# 270_rev_00.net
KiCad netlist of a schematic drawn in EAGLE
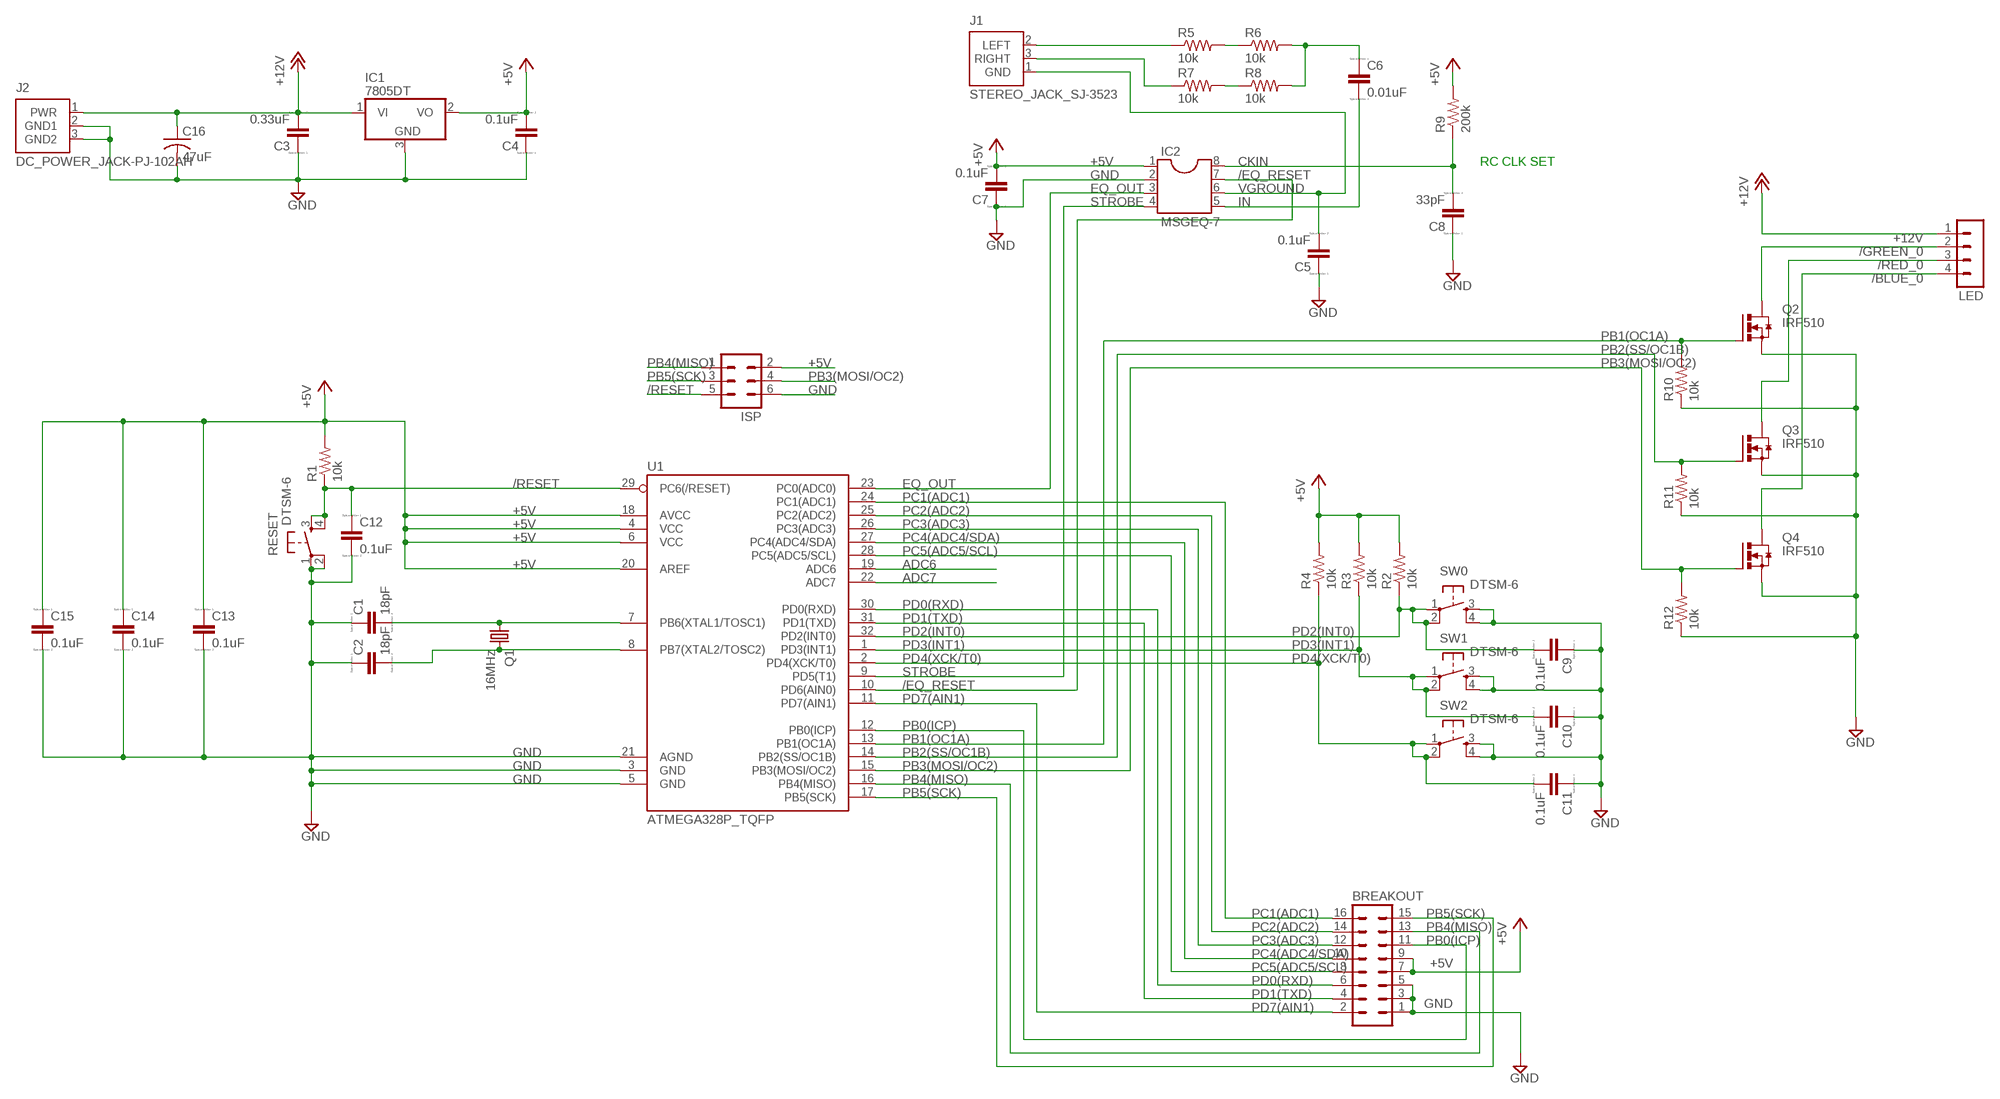
[diagram p0: schematic, sheet 1]

(export (version "E")
  (design (tool "Eeschema 10.0.6"))
  (components
    (comp (ref "BREAKOUT")
      (value "MA08-2")
      (footprint "eagle-import:MA08-2")
      (libsource (lib "eagle-import") (part "MA08-2"))
    )
    (comp (ref "C1")
      (value "18pF")
      (footprint "eagle-import:C0805K")
      (libsource (lib "eagle-import") (part "C-EUC0805K"))
    )
    (comp (ref "C2")
      (value "18pF")
      (footprint "eagle-import:C0805K")
      (libsource (lib "eagle-import") (part "C-EUC0805K"))
    )
    (comp (ref "C3")
      (value "0.33uF")
      (footprint "eagle-import:C0805K")
      (libsource (lib "eagle-import") (part "C-EUC0805K"))
    )
    (comp (ref "C4")
      (value "0.1uF")
      (footprint "eagle-import:C0805K")
      (libsource (lib "eagle-import") (part "C-EUC0805K"))
    )
    (comp (ref "C5")
      (value "0.1uF")
      (footprint "eagle-import:C0805K")
      (libsource (lib "eagle-import") (part "C-EUC0805K"))
    )
    (comp (ref "C6")
      (value "0.01uF")
      (footprint "eagle-import:C0805K")
      (libsource (lib "eagle-import") (part "C-EUC0805K"))
    )
    (comp (ref "C7")
      (value "0.1uF")
      (footprint "eagle-import:C0805K")
      (libsource (lib "eagle-import") (part "C-EUC0805K"))
    )
    (comp (ref "C8")
      (value "33pF")
      (footprint "eagle-import:C0805K")
      (libsource (lib "eagle-import") (part "C-EUC0805K"))
    )
    (comp (ref "C9")
      (value "0.1uF")
      (footprint "eagle-import:C0805K")
      (libsource (lib "eagle-import") (part "C-EUC0805K"))
    )
    (comp (ref "C10")
      (value "0.1uF")
      (footprint "eagle-import:C0805K")
      (libsource (lib "eagle-import") (part "C-EUC0805K"))
    )
    (comp (ref "C11")
      (value "0.1uF")
      (footprint "eagle-import:C0805K")
      (libsource (lib "eagle-import") (part "C-EUC0805K"))
    )
    (comp (ref "C12")
      (value "0.1uF")
      (footprint "eagle-import:C0805K")
      (libsource (lib "eagle-import") (part "C-EUC0805K"))
    )
    (comp (ref "C13")
      (value "0.1uF")
      (footprint "eagle-import:C0805K")
      (libsource (lib "eagle-import") (part "C-EUC0805K"))
    )
    (comp (ref "C14")
      (value "0.1uF")
      (footprint "eagle-import:C0805K")
      (libsource (lib "eagle-import") (part "C-EUC0805K"))
    )
    (comp (ref "C15")
      (value "0.1uF")
      (footprint "eagle-import:C0805K")
      (libsource (lib "eagle-import") (part "C-EUC0805K"))
    )
    (comp (ref "C16")
      (value "47uF")
      (footprint "eagle-import:C1210K")
      (libsource (lib "eagle-import") (part "C-USC1210K"))
    )
    (comp (ref "IC1")
      (value "7805DT")
      (footprint "eagle-import:TO252")
      (libsource (lib "eagle-import") (part "78DT05"))
    )
    (comp (ref "IC2")
      (value "MSGEQ-7")
      (footprint "eagle-import:DIL08")
      (libsource (lib "eagle-import") (part "DIL8"))
    )
    (comp (ref "ISP")
      (value "MA03-2")
      (footprint "eagle-import:MA03-2")
      (libsource (lib "eagle-import") (part "MA03-2"))
    )
    (comp (ref "J1")
      (value "STEREO_JACK_SJ-3523")
      (footprint "eagle-import:SJ-3523")
      (libsource (lib "eagle-import") (part "STEREO_JACK_SJ-3523"))
    )
    (comp (ref "J2")
      (value "DC_POWER_JACK-PJ-102AH")
      (footprint "eagle-import:PJ-102AH")
      (libsource (lib "eagle-import") (part "DC_POWER_JACK-PJ-102AH"))
    )
    (comp (ref "LED")
      (value "MA04-1")
      (footprint "eagle-import:MA04-1")
      (libsource (lib "eagle-import") (part "MA04-1"))
    )
    (comp (ref "Q1")
      (value "16MHz")
      (footprint "eagle-import:SM49")
      (libsource (lib "eagle-import") (part "CRYSTALSM49"))
    )
    (comp (ref "Q2")
      (value "IRF510")
      (footprint "eagle-import:D2PACK")
      (libsource (lib "eagle-import") (part "IRF3704S"))
    )
    (comp (ref "Q3")
      (value "IRF510")
      (footprint "eagle-import:D2PACK")
      (libsource (lib "eagle-import") (part "IRF3704S"))
    )
    (comp (ref "Q4")
      (value "IRF510")
      (footprint "eagle-import:D2PACK")
      (libsource (lib "eagle-import") (part "IRF3704S"))
    )
    (comp (ref "R1")
      (value "10k")
      (footprint "eagle-import:R0805")
      (libsource (lib "eagle-import") (part "R-US_R0805"))
    )
    (comp (ref "R2")
      (value "10k")
      (footprint "eagle-import:R0805")
      (libsource (lib "eagle-import") (part "R-US_R0805"))
    )
    (comp (ref "R3")
      (value "10k")
      (footprint "eagle-import:R0805")
      (libsource (lib "eagle-import") (part "R-US_R0805"))
    )
    (comp (ref "R4")
      (value "10k")
      (footprint "eagle-import:R0805")
      (libsource (lib "eagle-import") (part "R-US_R0805"))
    )
    (comp (ref "R5")
      (value "10k")
      (footprint "eagle-import:R0805")
      (libsource (lib "eagle-import") (part "R-US_R0805"))
    )
    (comp (ref "R6")
      (value "10k")
      (footprint "eagle-import:R0805")
      (libsource (lib "eagle-import") (part "R-US_R0805"))
    )
    (comp (ref "R7")
      (value "10k")
      (footprint "eagle-import:R0805")
      (libsource (lib "eagle-import") (part "R-US_R0805"))
    )
    (comp (ref "R8")
      (value "10k")
      (footprint "eagle-import:R0805")
      (libsource (lib "eagle-import") (part "R-US_R0805"))
    )
    (comp (ref "R9")
      (value "200k")
      (footprint "eagle-import:R0805")
      (libsource (lib "eagle-import") (part "R-US_R0805"))
    )
    (comp (ref "R10")
      (value "10k")
      (footprint "eagle-import:R0805")
      (libsource (lib "eagle-import") (part "R-US_R0805"))
    )
    (comp (ref "R11")
      (value "10k")
      (footprint "eagle-import:R0805")
      (libsource (lib "eagle-import") (part "R-US_R0805"))
    )
    (comp (ref "R12")
      (value "10k")
      (footprint "eagle-import:R0805")
      (libsource (lib "eagle-import") (part "R-US_R0805"))
    )
    (comp (ref "RESET")
      (value "DTSM-6")
      (footprint "eagle-import:DTSM-6")
      (libsource (lib "eagle-import") (part "DTSM-6"))
    )
    (comp (ref "SW0")
      (value "DTSM-6")
      (footprint "eagle-import:DTSM-6")
      (libsource (lib "eagle-import") (part "DTSM-6"))
    )
    (comp (ref "SW1")
      (value "DTSM-6")
      (footprint "eagle-import:DTSM-6")
      (libsource (lib "eagle-import") (part "DTSM-6"))
    )
    (comp (ref "SW2")
      (value "DTSM-6")
      (footprint "eagle-import:DTSM-6")
      (libsource (lib "eagle-import") (part "DTSM-6"))
    )
    (comp (ref "U1")
      (value "ATMEGA328P_TQFP")
      (footprint "eagle-import:TQFP32-08")
      (libsource (lib "eagle-import") (part "ATMEGA328P_TQFP"))
    )
  )
  (nets
    (net (code "1") (name "+5V") (class "Default")
      (node (ref "BREAKOUT") (pin "7") (pinfunction "7_7") (pintype "passive"))
      (node (ref "BREAKOUT") (pin "9") (pinfunction "9_9") (pintype "passive"))
      (node (ref "C13") (pin "1") (pinfunction "1_1") (pintype "passive"))
      (node (ref "C14") (pin "1") (pinfunction "1_1") (pintype "passive"))
      (node (ref "C15") (pin "1") (pinfunction "1_1") (pintype "passive"))
      (node (ref "C4") (pin "2") (pinfunction "2_2") (pintype "passive"))
      (node (ref "C7") (pin "2") (pinfunction "2_2") (pintype "passive"))
      (node (ref "IC1") (pin "2") (pinfunction "VO_2") (pintype "passive"))
      (node (ref "IC2") (pin "1") (pinfunction "1_1") (pintype "passive"))
      (node (ref "ISP") (pin "2") (pinfunction "2_2") (pintype "passive"))
      (node (ref "R1") (pin "2") (pinfunction "2_2") (pintype "passive"))
      (node (ref "R2") (pin "2") (pinfunction "2_2") (pintype "passive"))
      (node (ref "R3") (pin "2") (pinfunction "2_2") (pintype "passive"))
      (node (ref "R4") (pin "2") (pinfunction "2_2") (pintype "passive"))
      (node (ref "R9") (pin "2") (pinfunction "2_2") (pintype "passive"))
      (node (ref "U1") (pin "18") (pinfunction "AVCC_18") (pintype "bidirectional"))
      (node (ref "U1") (pin "20") (pinfunction "AREF_20") (pintype "bidirectional"))
      (node (ref "U1") (pin "4") (pinfunction "VCC_4") (pintype "bidirectional"))
      (node (ref "U1") (pin "6") (pinfunction "VCC_6") (pintype "bidirectional"))
    )
    (net (code "2") (name "+12V") (class "Default")
      (node (ref "C16") (pin "1") (pinfunction "1_1") (pintype "passive"))
      (node (ref "C3") (pin "2") (pinfunction "2_2") (pintype "passive"))
      (node (ref "IC1") (pin "1") (pinfunction "VI_1") (pintype "input"))
      (node (ref "J2") (pin "1") (pinfunction "PWR_1") (pintype "power_in"))
      (node (ref "LED") (pin "1") (pinfunction "1_1") (pintype "passive"))
    )
    (net (code "3") (name "/ADC6") (class "Default")
      (node (ref "U1") (pin "19") (pinfunction "ADC6_19") (pintype "bidirectional"))
    )
    (net (code "4") (name "/ADC7") (class "Default")
      (node (ref "U1") (pin "22") (pinfunction "ADC7_22") (pintype "bidirectional"))
    )
    (net (code "5") (name "/CKIN") (class "Default")
      (node (ref "C8") (pin "2") (pinfunction "2_2") (pintype "passive"))
      (node (ref "IC2") (pin "8") (pinfunction "8_8") (pintype "passive"))
      (node (ref "R9") (pin "1") (pinfunction "1_1") (pintype "passive"))
    )
    (net (code "6") (name "/EQ_OUT") (class "Default")
      (node (ref "IC2") (pin "3") (pinfunction "3_3") (pintype "passive"))
      (node (ref "U1") (pin "23") (pinfunction "PC0(ADC0)_23") (pintype "bidirectional"))
    )
    (net (code "7") (name "/IN") (class "Default")
      (node (ref "C6") (pin "2") (pinfunction "2_2") (pintype "passive"))
      (node (ref "IC2") (pin "5") (pinfunction "5_5") (pintype "passive"))
    )
    (net (code "8") (name "/PB0(ICP)") (class "Default")
      (node (ref "BREAKOUT") (pin "11") (pinfunction "11_11") (pintype "passive"))
      (node (ref "U1") (pin "12") (pinfunction "PB0(ICP)_12") (pintype "bidirectional"))
    )
    (net (code "9") (name "/PB1(OC1A)") (class "Default")
      (node (ref "Q2") (pin "1") (pinfunction "G_1") (pintype "passive"))
      (node (ref "R10") (pin "2") (pinfunction "2_2") (pintype "passive"))
      (node (ref "U1") (pin "13") (pinfunction "PB1(OC1A)_13") (pintype "bidirectional"))
    )
    (net (code "10") (name "/PB2(SS{slash}OC1B)") (class "Default")
      (node (ref "Q3") (pin "1") (pinfunction "G_1") (pintype "passive"))
      (node (ref "R11") (pin "2") (pinfunction "2_2") (pintype "passive"))
      (node (ref "U1") (pin "14") (pinfunction "PB2(SS/OC1B)_14") (pintype "bidirectional"))
    )
    (net (code "11") (name "/PB3(MOSI{slash}OC2)") (class "Default")
      (node (ref "ISP") (pin "4") (pinfunction "4_4") (pintype "passive"))
      (node (ref "Q4") (pin "1") (pinfunction "G_1") (pintype "passive"))
      (node (ref "R12") (pin "2") (pinfunction "2_2") (pintype "passive"))
      (node (ref "U1") (pin "15") (pinfunction "PB3(MOSI/OC2)_15") (pintype "bidirectional"))
    )
    (net (code "12") (name "/PB4(MISO)") (class "Default")
      (node (ref "BREAKOUT") (pin "13") (pinfunction "13_13") (pintype "passive"))
      (node (ref "ISP") (pin "1") (pinfunction "1_1") (pintype "passive"))
      (node (ref "U1") (pin "16") (pinfunction "PB4(MISO)_16") (pintype "bidirectional"))
    )
    (net (code "13") (name "/PB5(SCK)") (class "Default")
      (node (ref "BREAKOUT") (pin "15") (pinfunction "15_15") (pintype "passive"))
      (node (ref "ISP") (pin "3") (pinfunction "3_3") (pintype "passive"))
      (node (ref "U1") (pin "17") (pinfunction "PB5(SCK)_17") (pintype "bidirectional"))
    )
    (net (code "14") (name "/PC1(ADC1)") (class "Default")
      (node (ref "BREAKOUT") (pin "16") (pinfunction "16_16") (pintype "passive"))
      (node (ref "U1") (pin "24") (pinfunction "PC1(ADC1)_24") (pintype "bidirectional"))
    )
    (net (code "15") (name "/PC2(ADC2)") (class "Default")
      (node (ref "BREAKOUT") (pin "14") (pinfunction "14_14") (pintype "passive"))
      (node (ref "U1") (pin "25") (pinfunction "PC2(ADC2)_25") (pintype "bidirectional"))
    )
    (net (code "16") (name "/PC3(ADC3)") (class "Default")
      (node (ref "BREAKOUT") (pin "12") (pinfunction "12_12") (pintype "passive"))
      (node (ref "U1") (pin "26") (pinfunction "PC3(ADC3)_26") (pintype "bidirectional"))
    )
    (net (code "17") (name "/PC4(ADC4{slash}SDA)") (class "Default")
      (node (ref "BREAKOUT") (pin "10") (pinfunction "10_10") (pintype "passive"))
      (node (ref "U1") (pin "27") (pinfunction "PC4(ADC4/SDA)_27") (pintype "bidirectional"))
    )
    (net (code "18") (name "/PC5(ADC5{slash}SCL)") (class "Default")
      (node (ref "BREAKOUT") (pin "8") (pinfunction "8_8") (pintype "passive"))
      (node (ref "U1") (pin "28") (pinfunction "PC5(ADC5/SCL)_28") (pintype "bidirectional"))
    )
    (net (code "19") (name "/PD0(RXD)") (class "Default")
      (node (ref "BREAKOUT") (pin "6") (pinfunction "6_6") (pintype "passive"))
      (node (ref "U1") (pin "30") (pinfunction "PD0(RXD)_30") (pintype "bidirectional"))
    )
    (net (code "20") (name "/PD1(TXD)") (class "Default")
      (node (ref "BREAKOUT") (pin "4") (pinfunction "4_4") (pintype "passive"))
      (node (ref "U1") (pin "31") (pinfunction "PD1(TXD)_31") (pintype "bidirectional"))
    )
    (net (code "21") (name "/PD2(INT0)") (class "Default")
      (node (ref "C9") (pin "2") (pinfunction "2_2") (pintype "passive"))
      (node (ref "R2") (pin "1") (pinfunction "1_1") (pintype "passive"))
      (node (ref "SW0") (pin "1") (pinfunction "1_1") (pintype "passive"))
      (node (ref "SW0") (pin "2") (pinfunction "2_2") (pintype "passive"))
      (node (ref "U1") (pin "32") (pinfunction "PD2(INT0)_32") (pintype "bidirectional"))
    )
    (net (code "22") (name "/PD3(INT1)") (class "Default")
      (node (ref "C10") (pin "2") (pinfunction "2_2") (pintype "passive"))
      (node (ref "R3") (pin "1") (pinfunction "1_1") (pintype "passive"))
      (node (ref "SW1") (pin "1") (pinfunction "1_1") (pintype "passive"))
      (node (ref "SW1") (pin "2") (pinfunction "2_2") (pintype "passive"))
      (node (ref "U1") (pin "1") (pinfunction "PD3(INT1)_1") (pintype "bidirectional"))
    )
    (net (code "23") (name "/PD4(XCK{slash}T0)") (class "Default")
      (node (ref "C11") (pin "2") (pinfunction "2_2") (pintype "passive"))
      (node (ref "R4") (pin "1") (pinfunction "1_1") (pintype "passive"))
      (node (ref "SW2") (pin "1") (pinfunction "1_1") (pintype "passive"))
      (node (ref "SW2") (pin "2") (pinfunction "2_2") (pintype "passive"))
      (node (ref "U1") (pin "2") (pinfunction "PD4(XCK/T0)_2") (pintype "bidirectional"))
    )
    (net (code "24") (name "/PD7(AIN1)") (class "Default")
      (node (ref "BREAKOUT") (pin "2") (pinfunction "2_2") (pintype "passive"))
      (node (ref "U1") (pin "11") (pinfunction "PD7(AIN1)_11") (pintype "bidirectional"))
    )
    (net (code "25") (name "/STROBE") (class "Default")
      (node (ref "IC2") (pin "4") (pinfunction "4_4") (pintype "passive"))
      (node (ref "U1") (pin "9") (pinfunction "PD5(T1)_9") (pintype "bidirectional"))
    )
    (net (code "26") (name "/VGROUND") (class "Default")
      (node (ref "C5") (pin "2") (pinfunction "2_2") (pintype "passive"))
      (node (ref "IC2") (pin "6") (pinfunction "6_6") (pintype "passive"))
      (node (ref "J1") (pin "1") (pinfunction "GND_1") (pintype "power_in"))
    )
    (net (code "27") (name "/{slash}BLUE_0") (class "Default")
      (node (ref "LED") (pin "4") (pinfunction "4_4") (pintype "passive"))
      (node (ref "Q4") (pin "2") (pinfunction "D_2") (pintype "passive"))
    )
    (net (code "28") (name "/{slash}EQ_RESET") (class "Default")
      (node (ref "IC2") (pin "7") (pinfunction "7_7") (pintype "passive"))
      (node (ref "U1") (pin "10") (pinfunction "PD6(AIN0)_10") (pintype "bidirectional"))
    )
    (net (code "29") (name "/{slash}GREEN_0") (class "Default")
      (node (ref "LED") (pin "2") (pinfunction "2_2") (pintype "passive"))
      (node (ref "Q2") (pin "2") (pinfunction "D_2") (pintype "passive"))
    )
    (net (code "30") (name "/{slash}RED_0") (class "Default")
      (node (ref "LED") (pin "3") (pinfunction "3_3") (pintype "passive"))
      (node (ref "Q3") (pin "2") (pinfunction "D_2") (pintype "passive"))
    )
    (net (code "31") (name "/{slash}RESET") (class "Default")
      (node (ref "C12") (pin "1") (pinfunction "1_1") (pintype "passive"))
      (node (ref "ISP") (pin "5") (pinfunction "5_5") (pintype "passive"))
      (node (ref "R1") (pin "1") (pinfunction "1_1") (pintype "passive"))
      (node (ref "RESET") (pin "3") (pinfunction "3_3") (pintype "passive"))
      (node (ref "RESET") (pin "4") (pinfunction "4_4") (pintype "passive"))
      (node (ref "U1") (pin "29") (pinfunction "PC6(/RESET)_29") (pintype "bidirectional"))
    )
    (net (code "32") (name "GND") (class "Default")
      (node (ref "BREAKOUT") (pin "1") (pinfunction "1_1") (pintype "passive"))
      (node (ref "BREAKOUT") (pin "3") (pinfunction "3_3") (pintype "passive"))
      (node (ref "BREAKOUT") (pin "5") (pinfunction "5_5") (pintype "passive"))
      (node (ref "C1") (pin "1") (pinfunction "1_1") (pintype "passive"))
      (node (ref "C10") (pin "1") (pinfunction "1_1") (pintype "passive"))
      (node (ref "C11") (pin "1") (pinfunction "1_1") (pintype "passive"))
      (node (ref "C12") (pin "2") (pinfunction "2_2") (pintype "passive"))
      (node (ref "C13") (pin "2") (pinfunction "2_2") (pintype "passive"))
      (node (ref "C14") (pin "2") (pinfunction "2_2") (pintype "passive"))
      (node (ref "C15") (pin "2") (pinfunction "2_2") (pintype "passive"))
      (node (ref "C16") (pin "2") (pinfunction "2_2") (pintype "passive"))
      (node (ref "C2") (pin "1") (pinfunction "1_1") (pintype "passive"))
      (node (ref "C3") (pin "1") (pinfunction "1_1") (pintype "passive"))
      (node (ref "C4") (pin "1") (pinfunction "1_1") (pintype "passive"))
      (node (ref "C5") (pin "1") (pinfunction "1_1") (pintype "passive"))
      (node (ref "C7") (pin "1") (pinfunction "1_1") (pintype "passive"))
      (node (ref "C8") (pin "1") (pinfunction "1_1") (pintype "passive"))
      (node (ref "C9") (pin "1") (pinfunction "1_1") (pintype "passive"))
      (node (ref "IC1") (pin "3") (pinfunction "GND_3") (pintype "passive"))
      (node (ref "IC2") (pin "2") (pinfunction "2_2") (pintype "passive"))
      (node (ref "ISP") (pin "6") (pinfunction "6_6") (pintype "passive"))
      (node (ref "J2") (pin "2") (pinfunction "GND1_2") (pintype "power_in"))
      (node (ref "J2") (pin "3") (pinfunction "GND2_3") (pintype "power_in"))
      (node (ref "Q2") (pin "3") (pinfunction "S_3") (pintype "passive"))
      (node (ref "Q3") (pin "3") (pinfunction "S_3") (pintype "passive"))
      (node (ref "Q4") (pin "3") (pinfunction "S_3") (pintype "passive"))
      (node (ref "R10") (pin "1") (pinfunction "1_1") (pintype "passive"))
      (node (ref "R11") (pin "1") (pinfunction "1_1") (pintype "passive"))
      (node (ref "R12") (pin "1") (pinfunction "1_1") (pintype "passive"))
      (node (ref "RESET") (pin "1") (pinfunction "1_1") (pintype "passive"))
      (node (ref "RESET") (pin "2") (pinfunction "2_2") (pintype "passive"))
      (node (ref "SW0") (pin "3") (pinfunction "3_3") (pintype "passive"))
      (node (ref "SW0") (pin "4") (pinfunction "4_4") (pintype "passive"))
      (node (ref "SW1") (pin "3") (pinfunction "3_3") (pintype "passive"))
      (node (ref "SW1") (pin "4") (pinfunction "4_4") (pintype "passive"))
      (node (ref "SW2") (pin "3") (pinfunction "3_3") (pintype "passive"))
      (node (ref "SW2") (pin "4") (pinfunction "4_4") (pintype "passive"))
      (node (ref "U1") (pin "21") (pinfunction "AGND_21") (pintype "bidirectional"))
      (node (ref "U1") (pin "3") (pinfunction "GND_3") (pintype "bidirectional"))
      (node (ref "U1") (pin "5") (pinfunction "GND_5") (pintype "bidirectional"))
    )
    (net (code "33") (name "Net-(C6-Pad1)") (class "Default")
      (node (ref "C6") (pin "1") (pinfunction "1_1") (pintype "passive"))
      (node (ref "R6") (pin "2") (pinfunction "2_2") (pintype "passive"))
      (node (ref "R8") (pin "2") (pinfunction "2_2") (pintype "passive"))
    )
    (net (code "34") (name "Net-(J1-LEFT)") (class "Default")
      (node (ref "J1") (pin "2") (pinfunction "LEFT_2") (pintype "output"))
      (node (ref "R5") (pin "1") (pinfunction "1_1") (pintype "passive"))
    )
    (net (code "35") (name "Net-(J1-RIGHT)") (class "Default")
      (node (ref "J1") (pin "3") (pinfunction "RIGHT_3") (pintype "output"))
      (node (ref "R7") (pin "1") (pinfunction "1_1") (pintype "passive"))
    )
    (net (code "36") (name "Net-(R5-Pad2)") (class "Default")
      (node (ref "R5") (pin "2") (pinfunction "2_2") (pintype "passive"))
      (node (ref "R6") (pin "1") (pinfunction "1_1") (pintype "passive"))
    )
    (net (code "37") (name "Net-(R7-Pad2)") (class "Default")
      (node (ref "R7") (pin "2") (pinfunction "2_2") (pintype "passive"))
      (node (ref "R8") (pin "1") (pinfunction "1_1") (pintype "passive"))
    )
    (net (code "38") (name "Net-(U1-PB6(XTAL1{slash}TOSC1))") (class "Default")
      (node (ref "C1") (pin "2") (pinfunction "2_2") (pintype "passive"))
      (node (ref "Q1") (pin "1") (pinfunction "1_1") (pintype "passive"))
      (node (ref "U1") (pin "7") (pinfunction "PB6(XTAL1/TOSC1)_7") (pintype "bidirectional"))
    )
    (net (code "39") (name "Net-(U1-PB7(XTAL2{slash}TOSC2))") (class "Default")
      (node (ref "C2") (pin "2") (pinfunction "2_2") (pintype "passive"))
      (node (ref "Q1") (pin "2") (pinfunction "2_2") (pintype "passive"))
      (node (ref "U1") (pin "8") (pinfunction "PB7(XTAL2/TOSC2)_8") (pintype "bidirectional"))
    )
  )
)
